# tx.net
KiCad netlist of a schematic drawn in EAGLE
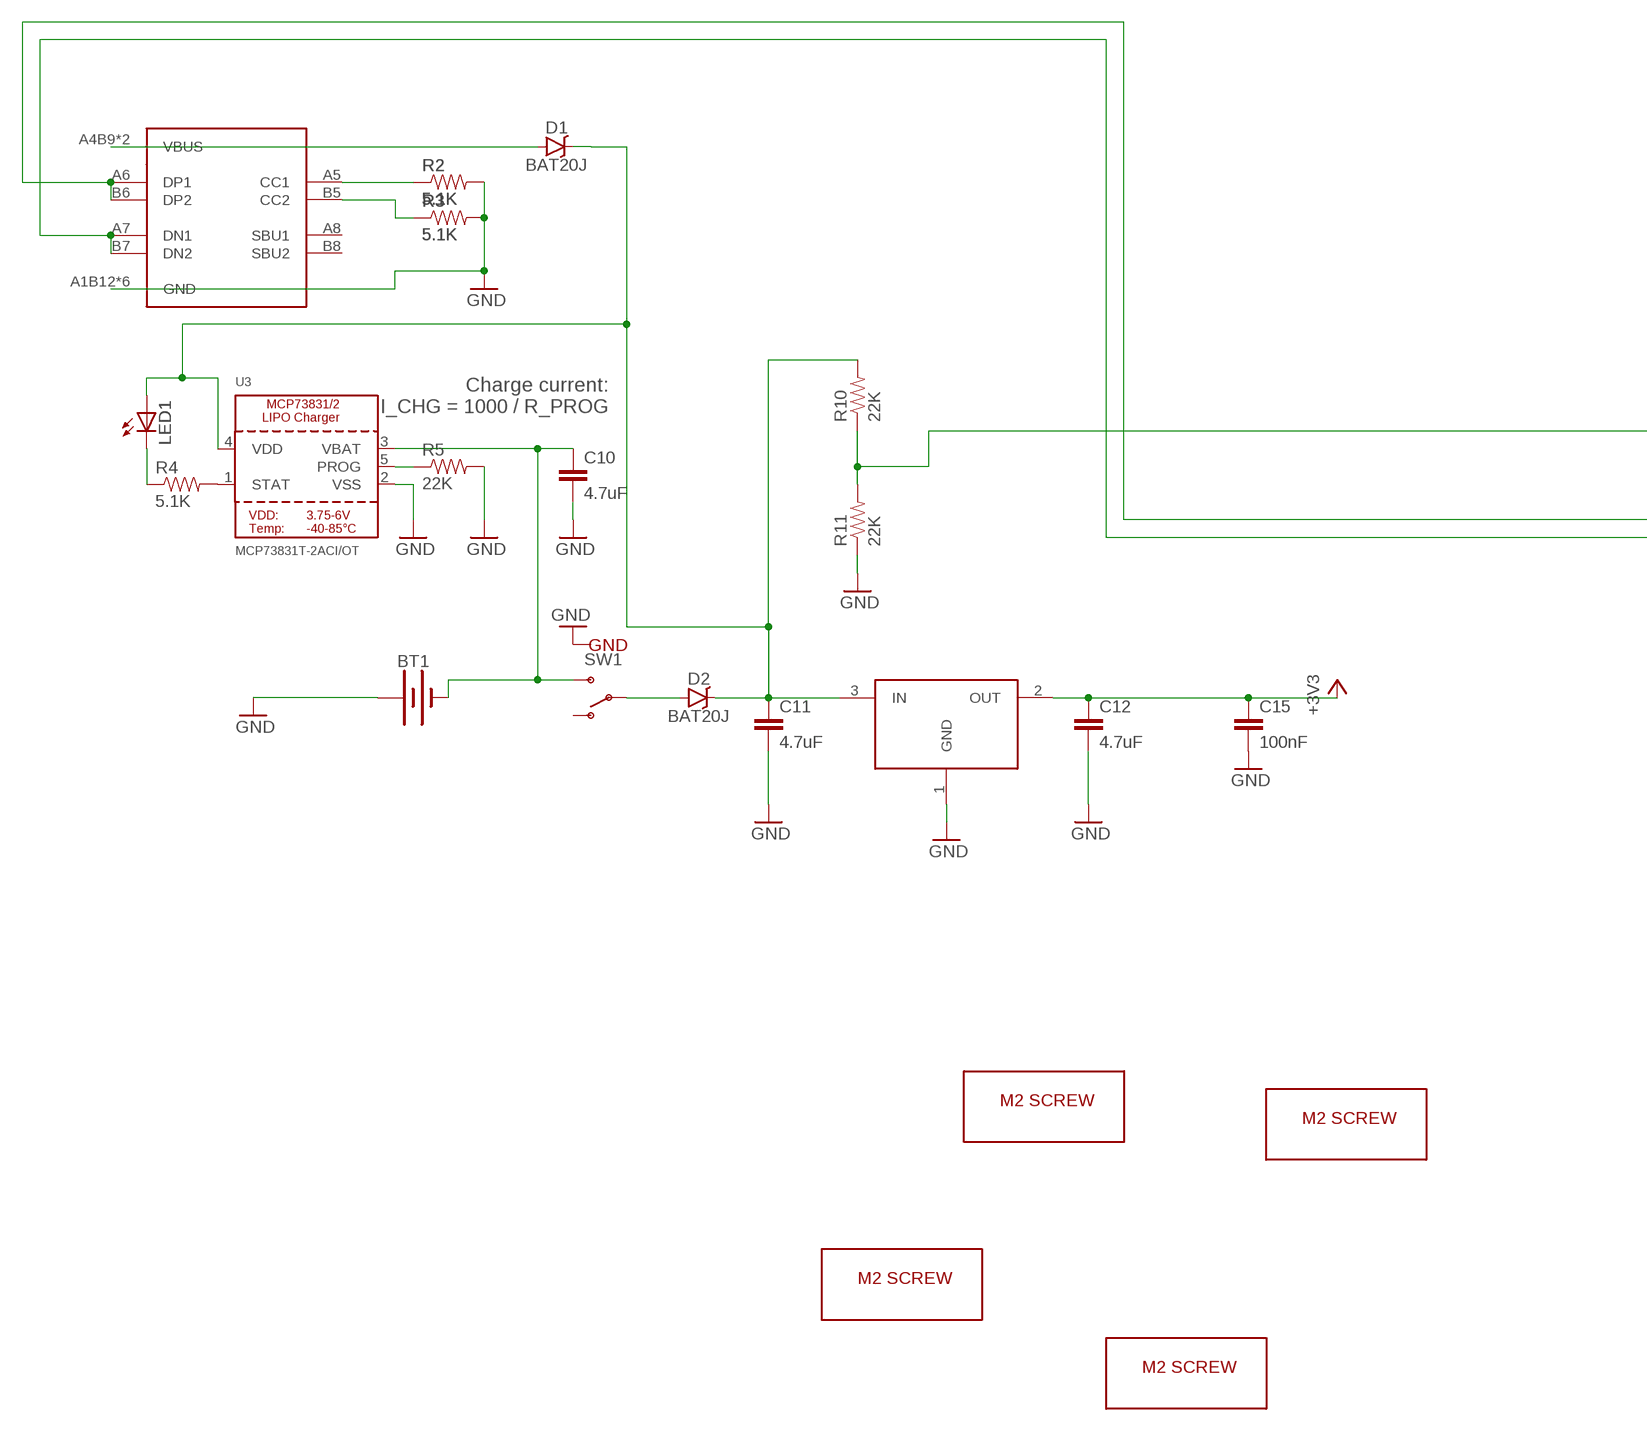
[diagram p0: schematic, sheet 1, part 1 of 2]
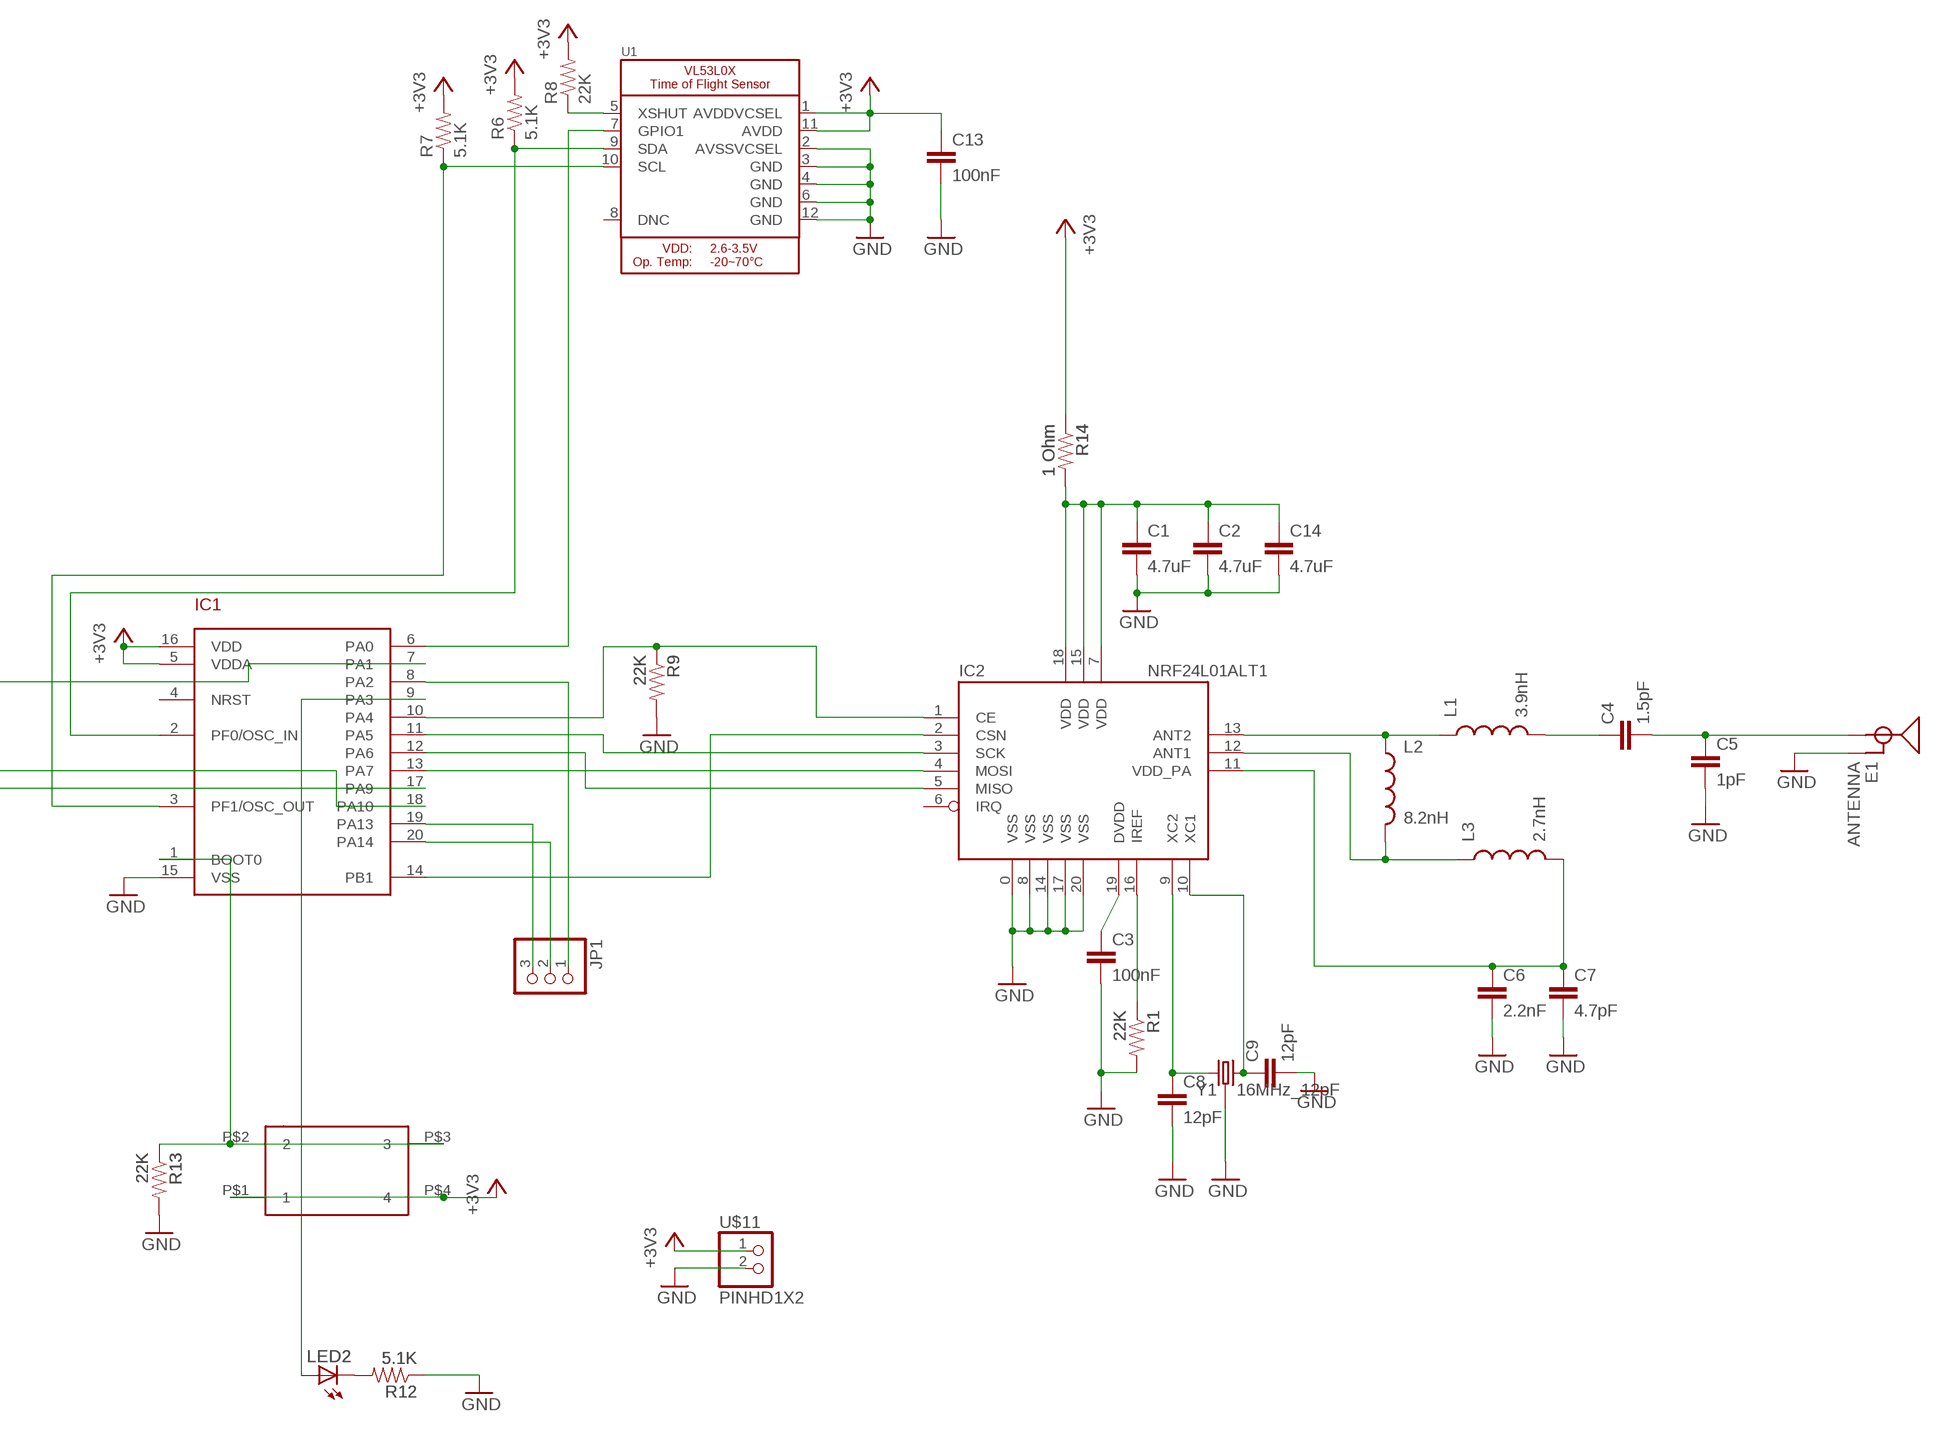
[diagram p1: schematic, sheet 1, part 2 of 2]

(export (version "E")
  (design (tool "Eeschema 10.0.6"))
  (components
    (comp (ref "BT1")
      (value "TX_SPARKFUN-BATTERIES_BATTERY-24.5MM_PTH")
      (footprint "eagle-import:TX_SPARKFUN-BATTERIES_BATTCON_24.5MM_PTH")
      (libsource (lib "eagle-import") (part "TX_SPARKFUN-BATTERIES_BATTERY-24.5MM_PTH"))
    )
    (comp (ref "C1")
      (value "4.7uF")
      (footprint "eagle-import:0805")
      (libsource (lib "eagle-import") (part "clock_CAP0805"))
    )
    (comp (ref "C2")
      (value "4.7uF")
      (footprint "eagle-import:0805")
      (libsource (lib "eagle-import") (part "clock_CAP0805"))
    )
    (comp (ref "C3")
      (value "100nF")
      (footprint "eagle-import:0805")
      (libsource (lib "eagle-import") (part "clock_CAP0805"))
    )
    (comp (ref "C4")
      (value "1.5pF")
      (footprint "eagle-import:0805")
      (libsource (lib "eagle-import") (part "clock_CAP0805"))
    )
    (comp (ref "C5")
      (value "1pF")
      (footprint "eagle-import:0805")
      (libsource (lib "eagle-import") (part "clock_CAP0805"))
    )
    (comp (ref "C6")
      (value "2.2nF")
      (footprint "eagle-import:0805")
      (libsource (lib "eagle-import") (part "clock_CAP0805"))
    )
    (comp (ref "C7")
      (value "4.7pF")
      (footprint "eagle-import:0805")
      (libsource (lib "eagle-import") (part "clock_CAP0805"))
    )
    (comp (ref "C8")
      (value "12pF")
      (footprint "eagle-import:0805")
      (libsource (lib "eagle-import") (part "clock_CAP0805"))
    )
    (comp (ref "C9")
      (value "12pF")
      (footprint "eagle-import:0805")
      (libsource (lib "eagle-import") (part "clock_CAP0805"))
    )
    (comp (ref "C10")
      (value "4.7uF")
      (footprint "eagle-import:0805")
      (libsource (lib "eagle-import") (part "CAP0805"))
    )
    (comp (ref "C11")
      (value "4.7uF")
      (footprint "eagle-import:0805")
      (libsource (lib "eagle-import") (part "clock_CAP0805"))
    )
    (comp (ref "C12")
      (value "4.7uF")
      (footprint "eagle-import:0805")
      (libsource (lib "eagle-import") (part "clock_CAP0805"))
    )
    (comp (ref "C13")
      (value "100nF")
      (footprint "eagle-import:0805")
      (libsource (lib "eagle-import") (part "clock_CAP0805"))
    )
    (comp (ref "C14")
      (value "4.7uF")
      (footprint "eagle-import:0805")
      (libsource (lib "eagle-import") (part "clock_CAP0805"))
    )
    (comp (ref "C15")
      (value "100nF")
      (footprint "eagle-import:0805")
      (libsource (lib "eagle-import") (part "clock_CAP0805"))
    )
    (comp (ref "D1")
      (value "BAT20J")
      (footprint "eagle-import:SOD-323")
      (libsource (lib "eagle-import") (part "DIODE-SCHOTTKY-BAT20J"))
    )
    (comp (ref "D2")
      (value "BAT20J")
      (footprint "eagle-import:SOD-323")
      (libsource (lib "eagle-import") (part "DIODE-SCHOTTKY-BAT20J"))
    )
    (comp (ref "E1")
      (value "ANTENNA")
      (footprint "eagle-import:TRACE_ANTENNA_2.4GHZ_25.7MM_TUNED")
      (libsource (lib "eagle-import") (part "ANTENNATRACE-TUNED"))
    )
    (comp (ref "IC1")
      (value "STM32F030F4")
      (footprint "eagle-import:TSSOP20")
      (libsource (lib "eagle-import") (part "STM32F030F4"))
    )
    (comp (ref "IC2")
      (value "NRF24L01ALT1")
      (footprint "eagle-import:QFN20_ALT1")
      (libsource (lib "eagle-import") (part "NRF24L01ALT1"))
    )
    (comp (ref "JP1")
      (value "PINHD-1X3CB")
      (footprint "eagle-import:1X03-CLEANBIG")
      (libsource (lib "eagle-import") (part "PINHD-1X3CB"))
    )
    (comp (ref "L1")
      (value "3.9nH")
      (footprint "eagle-import:0805")
      (libsource (lib "eagle-import") (part "INDUCTOR0805"))
    )
    (comp (ref "L2")
      (value "8.2nH")
      (footprint "eagle-import:0805")
      (libsource (lib "eagle-import") (part "INDUCTOR0805"))
    )
    (comp (ref "L3")
      (value "2.7nH")
      (footprint "eagle-import:0805")
      (libsource (lib "eagle-import") (part "INDUCTOR0805"))
    )
    (comp (ref "LED1")
      (value "LEDCHIP-LED0805")
      (footprint "eagle-import:CHIP-LED0805")
      (libsource (lib "eagle-import") (part "LEDCHIP-LED0805"))
    )
    (comp (ref "LED2")
      (value "LEDCHIP-LED0805")
      (footprint "eagle-import:CHIP-LED0805")
      (libsource (lib "eagle-import") (part "LEDCHIP-LED0805"))
    )
    (comp (ref "R1")
      (value "22K")
      (footprint "eagle-import:0805")
      (libsource (lib "eagle-import") (part "joyAnalog_RESISTOR0805-RES"))
    )
    (comp (ref "R2")
      (value "5.1K")
      (footprint "eagle-import:0805")
      (libsource (lib "eagle-import") (part "joyAnalog_RESISTOR0805-RES"))
    )
    (comp (ref "R3")
      (value "5.1K")
      (footprint "eagle-import:0805")
      (libsource (lib "eagle-import") (part "joyAnalog_RESISTOR0805-RES"))
    )
    (comp (ref "R4")
      (value "5.1K")
      (footprint "eagle-import:0805")
      (libsource (lib "eagle-import") (part "RESISTOR0805-RES"))
    )
    (comp (ref "R5")
      (value "22K")
      (footprint "eagle-import:0805")
      (libsource (lib "eagle-import") (part "RESISTOR0805-RES"))
    )
    (comp (ref "R6")
      (value "5.1K")
      (footprint "eagle-import:0805")
      (libsource (lib "eagle-import") (part "RESISTOR0805-RES"))
    )
    (comp (ref "R7")
      (value "5.1K")
      (footprint "eagle-import:0805")
      (libsource (lib "eagle-import") (part "RESISTOR0805-RES"))
    )
    (comp (ref "R8")
      (value "22K")
      (footprint "eagle-import:0805")
      (libsource (lib "eagle-import") (part "RESISTOR0805-RES"))
    )
    (comp (ref "R9")
      (value "22K")
      (footprint "eagle-import:0805")
      (libsource (lib "eagle-import") (part "joyAnalog_RESISTOR0805-RES"))
    )
    (comp (ref "R10")
      (value "22K")
      (footprint "eagle-import:0805")
      (libsource (lib "eagle-import") (part "RESISTOR0805-RES"))
    )
    (comp (ref "R11")
      (value "22K")
      (footprint "eagle-import:0805")
      (libsource (lib "eagle-import") (part "RESISTOR0805-RES"))
    )
    (comp (ref "R12")
      (value "5.1K")
      (footprint "eagle-import:0805")
      (libsource (lib "eagle-import") (part "joyAnalog_RESISTOR0805-RES"))
    )
    (comp (ref "R13")
      (value "22K")
      (footprint "eagle-import:0805")
      (libsource (lib "eagle-import") (part "joyAnalog_RESISTOR0805-RES"))
    )
    (comp (ref "R14")
      (value "1 Ohm")
      (footprint "eagle-import:0805")
      (libsource (lib "eagle-import") (part "joyAnalog_RESISTOR0805-RES"))
    )
    (comp (ref "SW1")
      (value "SWITCH-SPDTTDFGDFG")
      (footprint "eagle-import:SWITCH-SPST-SMD-A")
      (libsource (lib "eagle-import") (part "SWITCH-SPDTTDFGDFG"))
    )
    (comp (ref "SW2")
      (value "324_SW324_SWITCH_FOOT_HOLE")
      (footprint "eagle-import:342_SWICH_FOOT_HOLE")
      (libsource (lib "eagle-import") (part "324_SW324_SWITCH_FOOT_HOLE"))
    )
    (comp (ref "U$1")
      (value "M2_SCREW_DEV")
      (footprint "eagle-import:M2_SCREW_FOOT")
      (libsource (lib "eagle-import") (part "M2_SCREW_DEV"))
    )
    (comp (ref "U$11")
      (value "PINHD1X2")
      (footprint "eagle-import:1X02")
      (libsource (lib "eagle-import") (part "PINHD1X2"))
    )
    (comp (ref "U$12")
      (value "M2_SCREW_DEV")
      (footprint "eagle-import:M2_SCREW_FOOT")
      (libsource (lib "eagle-import") (part "M2_SCREW_DEV"))
    )
    (comp (ref "U$13")
      (value "M2_SCREW_DEV")
      (footprint "eagle-import:M2_SCREW_FOOT")
      (libsource (lib "eagle-import") (part "M2_SCREW_DEV"))
    )
    (comp (ref "U$14")
      (value "M2_SCREW_DEV")
      (footprint "eagle-import:M2_SCREW_FOOT")
      (libsource (lib "eagle-import") (part "M2_SCREW_DEV"))
    )
    (comp (ref "U1")
      (value "VL53L0X")
      (footprint "eagle-import:LGA12_ST")
      (libsource (lib "eagle-import") (part "VL53L0X"))
    )
    (comp (ref "U2")
      (value "USBC_16P")
      (footprint "eagle-import:USBC_16P_FOOT")
      (libsource (lib "eagle-import") (part "USBC_16P"))
    )
    (comp (ref "U3")
      (value "MCP73831T-2ACI/OT")
      (footprint "eagle-import:SOT23-5")
      (libsource (lib "eagle-import") (part "MCP73831/2"))
    )
    (comp (ref "U4")
      (value "XC6206_DEV")
      (footprint "eagle-import:SOT23R_INFINEON")
      (libsource (lib "eagle-import") (part "XC6206_DEV"))
    )
    (comp (ref "Y1")
      (value "16MHz_12pF")
      (footprint "eagle-import:CRYSTAL-SMD-3.2X2.5MM")
      (libsource (lib "eagle-import") (part "CRYSTAL-26MHZSMD-3.2X2.5"))
    )
  )
  (nets
    (net (code "1") (name "+3V3") (class "Default")
      (node (ref "C12") (pin "1") (pinfunction "1_1") (pintype "passive"))
      (node (ref "C13") (pin "1") (pinfunction "1_1") (pintype "passive"))
      (node (ref "C15") (pin "1") (pinfunction "1_1") (pintype "passive"))
      (node (ref "IC1") (pin "16") (pinfunction "VDD_16") (pintype "bidirectional"))
      (node (ref "IC1") (pin "5") (pinfunction "VDDA_5") (pintype "bidirectional"))
      (node (ref "R14") (pin "1") (pinfunction "1_1") (pintype "passive"))
      (node (ref "R6") (pin "2") (pinfunction "2_2") (pintype "passive"))
      (node (ref "R7") (pin "2") (pinfunction "2_2") (pintype "passive"))
      (node (ref "R8") (pin "2") (pinfunction "2_2") (pintype "passive"))
      (node (ref "SW2") (pin "P$1") (pinfunction "1_P$1") (pintype "bidirectional"))
      (node (ref "SW2") (pin "P$4") (pinfunction "4_P$4") (pintype "bidirectional"))
      (node (ref "U$11") (pin "1") (pinfunction "1_1") (pintype "passive"))
      (node (ref "U1") (pin "1") (pinfunction "AVDDVCSEL_1") (pintype "power_in"))
      (node (ref "U1") (pin "11") (pinfunction "AVDD_11") (pintype "power_in"))
      (node (ref "U4") (pin "2") (pinfunction "OUT_2") (pintype "bidirectional"))
    )
    (net (code "2") (name "GND") (class "Default")
      (node (ref "BT1") (pin "2") (pinfunction "+_2") (pintype "power_in"))
      (node (ref "C1") (pin "2") (pinfunction "2_2") (pintype "passive"))
      (node (ref "C10") (pin "2") (pinfunction "2_2") (pintype "passive"))
      (node (ref "C11") (pin "2") (pinfunction "2_2") (pintype "passive"))
      (node (ref "C12") (pin "2") (pinfunction "2_2") (pintype "passive"))
      (node (ref "C13") (pin "2") (pinfunction "2_2") (pintype "passive"))
      (node (ref "C14") (pin "2") (pinfunction "2_2") (pintype "passive"))
      (node (ref "C15") (pin "2") (pinfunction "2_2") (pintype "passive"))
      (node (ref "C2") (pin "2") (pinfunction "2_2") (pintype "passive"))
      (node (ref "C3") (pin "2") (pinfunction "2_2") (pintype "passive"))
      (node (ref "C5") (pin "2") (pinfunction "2_2") (pintype "passive"))
      (node (ref "C6") (pin "2") (pinfunction "2_2") (pintype "passive"))
      (node (ref "C7") (pin "2") (pinfunction "2_2") (pintype "passive"))
      (node (ref "C8") (pin "2") (pinfunction "2_2") (pintype "passive"))
      (node (ref "C9") (pin "2") (pinfunction "2_2") (pintype "passive"))
      (node (ref "E1") (pin "GND") (pinfunction "GND_GND") (pintype "bidirectional"))
      (node (ref "E1") (pin "GND2") (pinfunction "GND_GND2") (pintype "bidirectional"))
      (node (ref "IC1") (pin "15") (pinfunction "VSS_15") (pintype "bidirectional"))
      (node (ref "IC2") (pin "0") (pinfunction "VSS_0") (pintype "power_in"))
      (node (ref "IC2") (pin "14") (pinfunction "VSS_14") (pintype "power_in"))
      (node (ref "IC2") (pin "17") (pinfunction "VSS_17") (pintype "power_in"))
      (node (ref "IC2") (pin "20") (pinfunction "VSS_20") (pintype "power_in"))
      (node (ref "IC2") (pin "8") (pinfunction "VSS_8") (pintype "power_in"))
      (node (ref "R1") (pin "2") (pinfunction "2_2") (pintype "passive"))
      (node (ref "R11") (pin "1") (pinfunction "1_1") (pintype "passive"))
      (node (ref "R12") (pin "1") (pinfunction "1_1") (pintype "passive"))
      (node (ref "R13") (pin "2") (pinfunction "2_2") (pintype "passive"))
      (node (ref "R2") (pin "2") (pinfunction "2_2") (pintype "passive"))
      (node (ref "R3") (pin "2") (pinfunction "2_2") (pintype "passive"))
      (node (ref "R5") (pin "2") (pinfunction "2_2") (pintype "passive"))
      (node (ref "R9") (pin "2") (pinfunction "2_2") (pintype "passive"))
      (node (ref "SW1") (pin "G1") (pinfunction "GND_G1") (pintype "passive"))
      (node (ref "SW1") (pin "G2") (pinfunction "GND_G2") (pintype "passive"))
      (node (ref "SW1") (pin "G3") (pinfunction "GND_G3") (pintype "passive"))
      (node (ref "SW1") (pin "G4") (pinfunction "GND_G4") (pintype "passive"))
      (node (ref "U$11") (pin "2") (pinfunction "2_2") (pintype "passive"))
      (node (ref "U1") (pin "12") (pinfunction "GND_12") (pintype "power_in"))
      (node (ref "U1") (pin "2") (pinfunction "AVSSVCSEL_2") (pintype "power_in"))
      (node (ref "U1") (pin "3") (pinfunction "GND_3") (pintype "power_in"))
      (node (ref "U1") (pin "4") (pinfunction "GND_4") (pintype "power_in"))
      (node (ref "U1") (pin "6") (pinfunction "GND_6") (pintype "power_in"))
      (node (ref "U2") (pin "A1B12") (pinfunction "GND_A1B12") (pintype "bidirectional"))
      (node (ref "U2") (pin "B11A12") (pinfunction "GND_B11A12") (pintype "bidirectional"))
      (node (ref "U2") (pin "P$13") (pinfunction "GND_P$13") (pintype "bidirectional"))
      (node (ref "U2") (pin "P$14") (pinfunction "GND_P$14") (pintype "bidirectional"))
      (node (ref "U2") (pin "P$15") (pinfunction "GND_P$15") (pintype "bidirectional"))
      (node (ref "U2") (pin "P$16") (pinfunction "GND_P$16") (pintype "bidirectional"))
      (node (ref "U3") (pin "2") (pinfunction "VSS_2") (pintype "power_in"))
      (node (ref "U4") (pin "1") (pinfunction "GND_1") (pintype "bidirectional"))
      (node (ref "Y1") (pin "2") (pinfunction "3_2") (pintype "passive"))
      (node (ref "Y1") (pin "4") (pinfunction "3_4") (pintype "passive"))
    )
    (net (code "3") (name "Net-(BT1--)") (class "Default")
      (node (ref "BT1") (pin "1") (pinfunction "-_1") (pintype "power_in"))
      (node (ref "C10") (pin "1") (pinfunction "1_1") (pintype "passive"))
      (node (ref "SW1") (pin "3") (pinfunction "S_3") (pintype "passive"))
      (node (ref "U3") (pin "3") (pinfunction "VBAT_3") (pintype "power_in"))
    )
    (net (code "4") (name "Net-(C1-Pad1)") (class "Default")
      (node (ref "C1") (pin "1") (pinfunction "1_1") (pintype "passive"))
      (node (ref "C14") (pin "1") (pinfunction "1_1") (pintype "passive"))
      (node (ref "C2") (pin "1") (pinfunction "1_1") (pintype "passive"))
      (node (ref "IC2") (pin "15") (pinfunction "VDD_15") (pintype "power_in"))
      (node (ref "IC2") (pin "18") (pinfunction "VDD_18") (pintype "power_in"))
      (node (ref "IC2") (pin "7") (pinfunction "VDD_7") (pintype "power_in"))
      (node (ref "R14") (pin "2") (pinfunction "2_2") (pintype "passive"))
    )
    (net (code "5") (name "Net-(C4-Pad1)") (class "Default")
      (node (ref "C4") (pin "1") (pinfunction "1_1") (pintype "passive"))
      (node (ref "L1") (pin "2") (pinfunction "2_2") (pintype "passive"))
    )
    (net (code "6") (name "Net-(D1-PadA)") (class "Default")
      (node (ref "D1") (pin "A") (pinfunction "A_A") (pintype "passive"))
      (node (ref "U2") (pin "A4B9") (pinfunction "VBUS_A4B9") (pintype "bidirectional"))
      (node (ref "U2") (pin "B4A9") (pinfunction "VBUS_B4A9") (pintype "bidirectional"))
    )
    (net (code "7") (name "Net-(E1-SIGNAL)") (class "Default")
      (node (ref "C4") (pin "2") (pinfunction "2_2") (pintype "passive"))
      (node (ref "C5") (pin "1") (pinfunction "1_1") (pintype "passive"))
      (node (ref "E1") (pin "ANT") (pinfunction "SIGNAL_ANT") (pintype "bidirectional"))
    )
    (net (code "8") (name "Net-(IC1-BOOT0)") (class "Default")
      (node (ref "IC1") (pin "1") (pinfunction "BOOT0_1") (pintype "bidirectional"))
      (node (ref "R13") (pin "1") (pinfunction "1_1") (pintype "passive"))
      (node (ref "SW2") (pin "P$2") (pinfunction "2_P$2") (pintype "bidirectional"))
      (node (ref "SW2") (pin "P$3") (pinfunction "3_P$3") (pintype "bidirectional"))
    )
    (net (code "9") (name "Net-(IC1-PA0)") (class "Default")
      (node (ref "IC1") (pin "6") (pinfunction "PA0_6") (pintype "bidirectional"))
      (node (ref "U1") (pin "7") (pinfunction "GPIO1_7") (pintype "output"))
    )
    (net (code "10") (name "Net-(IC1-PA1)") (class "Default")
      (node (ref "IC1") (pin "7") (pinfunction "PA1_7") (pintype "bidirectional"))
      (node (ref "R10") (pin "1") (pinfunction "1_1") (pintype "passive"))
      (node (ref "R11") (pin "2") (pinfunction "2_2") (pintype "passive"))
    )
    (net (code "11") (name "Net-(IC1-PA2)") (class "Default")
      (node (ref "IC1") (pin "8") (pinfunction "PA2_8") (pintype "bidirectional"))
      (node (ref "JP1") (pin "1") (pinfunction "1_1") (pintype "passive"))
    )
    (net (code "12") (name "Net-(IC1-PA3)") (class "Default")
      (node (ref "IC1") (pin "9") (pinfunction "PA3_9") (pintype "bidirectional"))
      (node (ref "LED2") (pin "A") (pinfunction "A_A") (pintype "passive"))
    )
    (net (code "13") (name "Net-(IC1-PA4)") (class "Default")
      (node (ref "IC1") (pin "10") (pinfunction "PA4_10") (pintype "bidirectional"))
      (node (ref "IC2") (pin "1") (pinfunction "CE_1") (pintype "input"))
      (node (ref "R9") (pin "1") (pinfunction "1_1") (pintype "passive"))
    )
    (net (code "14") (name "Net-(IC1-PA5)") (class "Default")
      (node (ref "IC1") (pin "11") (pinfunction "PA5_11") (pintype "bidirectional"))
      (node (ref "IC2") (pin "3") (pinfunction "SCK_3") (pintype "input"))
    )
    (net (code "15") (name "Net-(IC1-PA6)") (class "Default")
      (node (ref "IC1") (pin "12") (pinfunction "PA6_12") (pintype "bidirectional"))
      (node (ref "IC2") (pin "5") (pinfunction "MISO_5") (pintype "output"))
    )
    (net (code "16") (name "Net-(IC1-PA7)") (class "Default")
      (node (ref "IC1") (pin "13") (pinfunction "PA7_13") (pintype "bidirectional"))
      (node (ref "IC2") (pin "4") (pinfunction "MOSI_4") (pintype "input"))
    )
    (net (code "17") (name "Net-(IC1-PA9)") (class "Default")
      (node (ref "IC1") (pin "17") (pinfunction "PA9_17") (pintype "bidirectional"))
      (node (ref "U2") (pin "A7") (pinfunction "DN1_A7") (pintype "bidirectional"))
      (node (ref "U2") (pin "B7") (pinfunction "DN2_B7") (pintype "bidirectional"))
    )
    (net (code "18") (name "Net-(IC1-PA10)") (class "Default")
      (node (ref "IC1") (pin "18") (pinfunction "PA10_18") (pintype "bidirectional"))
      (node (ref "U2") (pin "A6") (pinfunction "DP1_A6") (pintype "bidirectional"))
      (node (ref "U2") (pin "B6") (pinfunction "DP2_B6") (pintype "bidirectional"))
    )
    (net (code "19") (name "Net-(IC1-PA13)") (class "Default")
      (node (ref "IC1") (pin "19") (pinfunction "PA13_19") (pintype "bidirectional"))
      (node (ref "JP1") (pin "3") (pinfunction "3_3") (pintype "passive"))
    )
    (net (code "20") (name "Net-(IC1-PA14)") (class "Default")
      (node (ref "IC1") (pin "20") (pinfunction "PA14_20") (pintype "bidirectional"))
      (node (ref "JP1") (pin "2") (pinfunction "2_2") (pintype "passive"))
    )
    (net (code "21") (name "Net-(IC1-PB1)") (class "Default")
      (node (ref "IC1") (pin "14") (pinfunction "PB1_14") (pintype "bidirectional"))
      (node (ref "IC2") (pin "2") (pinfunction "CSN_2") (pintype "input"))
    )
    (net (code "22") (name "Net-(IC1-PF0{slash}OSC_IN)") (class "Default")
      (node (ref "IC1") (pin "2") (pinfunction "PF0/OSC_IN_2") (pintype "bidirectional"))
      (node (ref "R6") (pin "1") (pinfunction "1_1") (pintype "passive"))
      (node (ref "U1") (pin "9") (pinfunction "SDA_9") (pintype "open_collector"))
    )
    (net (code "23") (name "Net-(IC1-PF1{slash}OSC_OUT)") (class "Default")
      (node (ref "IC1") (pin "3") (pinfunction "PF1/OSC_OUT_3") (pintype "bidirectional"))
      (node (ref "R7") (pin "1") (pinfunction "1_1") (pintype "passive"))
      (node (ref "U1") (pin "10") (pinfunction "SCL_10") (pintype "open_collector"))
    )
    (net (code "24") (name "Net-(IC2-ANT1)") (class "Default")
      (node (ref "IC2") (pin "12") (pinfunction "ANT1_12") (pintype "output"))
      (node (ref "L2") (pin "2") (pinfunction "2_2") (pintype "passive"))
      (node (ref "L3") (pin "1") (pinfunction "1_1") (pintype "passive"))
    )
    (net (code "25") (name "Net-(IC2-ANT2)") (class "Default")
      (node (ref "IC2") (pin "13") (pinfunction "ANT2_13") (pintype "output"))
      (node (ref "L1") (pin "1") (pinfunction "1_1") (pintype "passive"))
      (node (ref "L2") (pin "1") (pinfunction "1_1") (pintype "passive"))
    )
    (net (code "26") (name "Net-(IC2-DVDD)") (class "Default")
      (node (ref "C3") (pin "1") (pinfunction "1_1") (pintype "passive"))
      (node (ref "IC2") (pin "19") (pinfunction "DVDD_19") (pintype "power_in"))
    )
    (net (code "27") (name "Net-(IC2-IREF)") (class "Default")
      (node (ref "IC2") (pin "16") (pinfunction "IREF_16") (pintype "input"))
      (node (ref "R1") (pin "1") (pinfunction "1_1") (pintype "passive"))
    )
    (net (code "28") (name "Net-(IC2-VDD_PA)") (class "Default")
      (node (ref "C6") (pin "1") (pinfunction "1_1") (pintype "passive"))
      (node (ref "C7") (pin "1") (pinfunction "1_1") (pintype "passive"))
      (node (ref "IC2") (pin "11") (pinfunction "VDD_PA_11") (pintype "power_in"))
      (node (ref "L3") (pin "2") (pinfunction "2_2") (pintype "passive"))
    )
    (net (code "29") (name "Net-(IC2-XC1)") (class "Default")
      (node (ref "C9") (pin "1") (pinfunction "1_1") (pintype "passive"))
      (node (ref "IC2") (pin "10") (pinfunction "XC1_10") (pintype "input"))
      (node (ref "Y1") (pin "3") (pinfunction "2_3") (pintype "passive"))
    )
    (net (code "30") (name "Net-(IC2-XC2)") (class "Default")
      (node (ref "C8") (pin "1") (pinfunction "1_1") (pintype "passive"))
      (node (ref "IC2") (pin "9") (pinfunction "XC2_9") (pintype "input"))
      (node (ref "Y1") (pin "1") (pinfunction "1_1") (pintype "passive"))
    )
    (net (code "31") (name "Net-(LED1-PadC)") (class "Default")
      (node (ref "LED1") (pin "C") (pinfunction "C_C") (pintype "passive"))
      (node (ref "R4") (pin "1") (pinfunction "1_1") (pintype "passive"))
    )
    (net (code "32") (name "Net-(LED2-PadC)") (class "Default")
      (node (ref "LED2") (pin "C") (pinfunction "C_C") (pintype "passive"))
      (node (ref "R12") (pin "2") (pinfunction "2_2") (pintype "passive"))
    )
    (net (code "33") (name "Net-(SW1-P)") (class "Default")
      (node (ref "D2") (pin "A") (pinfunction "A_A") (pintype "passive"))
      (node (ref "SW1") (pin "2") (pinfunction "P_2") (pintype "passive"))
    )
    (net (code "34") (name "Net-(U1-XSHUT)") (class "Default")
      (node (ref "R8") (pin "1") (pinfunction "1_1") (pintype "passive"))
      (node (ref "U1") (pin "5") (pinfunction "XSHUT_5") (pintype "input"))
    )
    (net (code "35") (name "Net-(U2-CC1)") (class "Default")
      (node (ref "R2") (pin "1") (pinfunction "1_1") (pintype "passive"))
      (node (ref "U2") (pin "A5") (pinfunction "CC1_A5") (pintype "bidirectional"))
    )
    (net (code "36") (name "Net-(U2-CC2)") (class "Default")
      (node (ref "R3") (pin "1") (pinfunction "1_1") (pintype "passive"))
      (node (ref "U2") (pin "B5") (pinfunction "CC2_B5") (pintype "bidirectional"))
    )
    (net (code "37") (name "Net-(U3-PROG)") (class "Default")
      (node (ref "R5") (pin "1") (pinfunction "1_1") (pintype "passive"))
      (node (ref "U3") (pin "5") (pinfunction "PROG_5") (pintype "input"))
    )
    (net (code "38") (name "Net-(U3-STAT)") (class "Default")
      (node (ref "R4") (pin "2") (pinfunction "2_2") (pintype "passive"))
      (node (ref "U3") (pin "1") (pinfunction "STAT_1") (pintype "output"))
    )
    (net (code "39") (name "Net-(U3-VDD)") (class "Default")
      (node (ref "C11") (pin "1") (pinfunction "1_1") (pintype "passive"))
      (node (ref "D1") (pin "C") (pinfunction "C_C") (pintype "passive"))
      (node (ref "D2") (pin "C") (pinfunction "C_C") (pintype "passive"))
      (node (ref "LED1") (pin "A") (pinfunction "A_A") (pintype "passive"))
      (node (ref "R10") (pin "2") (pinfunction "2_2") (pintype "passive"))
      (node (ref "U3") (pin "4") (pinfunction "VDD_4") (pintype "power_in"))
      (node (ref "U4") (pin "3") (pinfunction "IN_3") (pintype "bidirectional"))
    )
    (net (code "40") (name "unconnected-(IC1-NRST-Pad4)") (class "Default")
      (node (ref "IC1") (pin "4") (pinfunction "NRST_4") (pintype "bidirectional"))
    )
    (net (code "41") (name "unconnected-(IC2-IRQ-Pad6)") (class "Default")
      (node (ref "IC2") (pin "6") (pinfunction "IRQ_6") (pintype "output"))
    )
    (net (code "42") (name "unconnected-(SW1-O-Pad1)") (class "Default")
      (node (ref "SW1") (pin "1") (pinfunction "O_1") (pintype "passive"))
    )
    (net (code "43") (name "unconnected-(U1-DNC-Pad8)") (class "Default")
      (node (ref "U1") (pin "8") (pinfunction "DNC_8") (pintype "no_connect"))
    )
    (net (code "44") (name "unconnected-(U2-SBU1-PadA8)") (class "Default")
      (node (ref "U2") (pin "A8") (pinfunction "SBU1_A8") (pintype "bidirectional"))
    )
    (net (code "45") (name "unconnected-(U2-SBU2-PadB8)") (class "Default")
      (node (ref "U2") (pin "B8") (pinfunction "SBU2_B8") (pintype "bidirectional"))
    )
  )
)
